# schematic.net
KiCad netlist of a schematic drawn in EAGLE
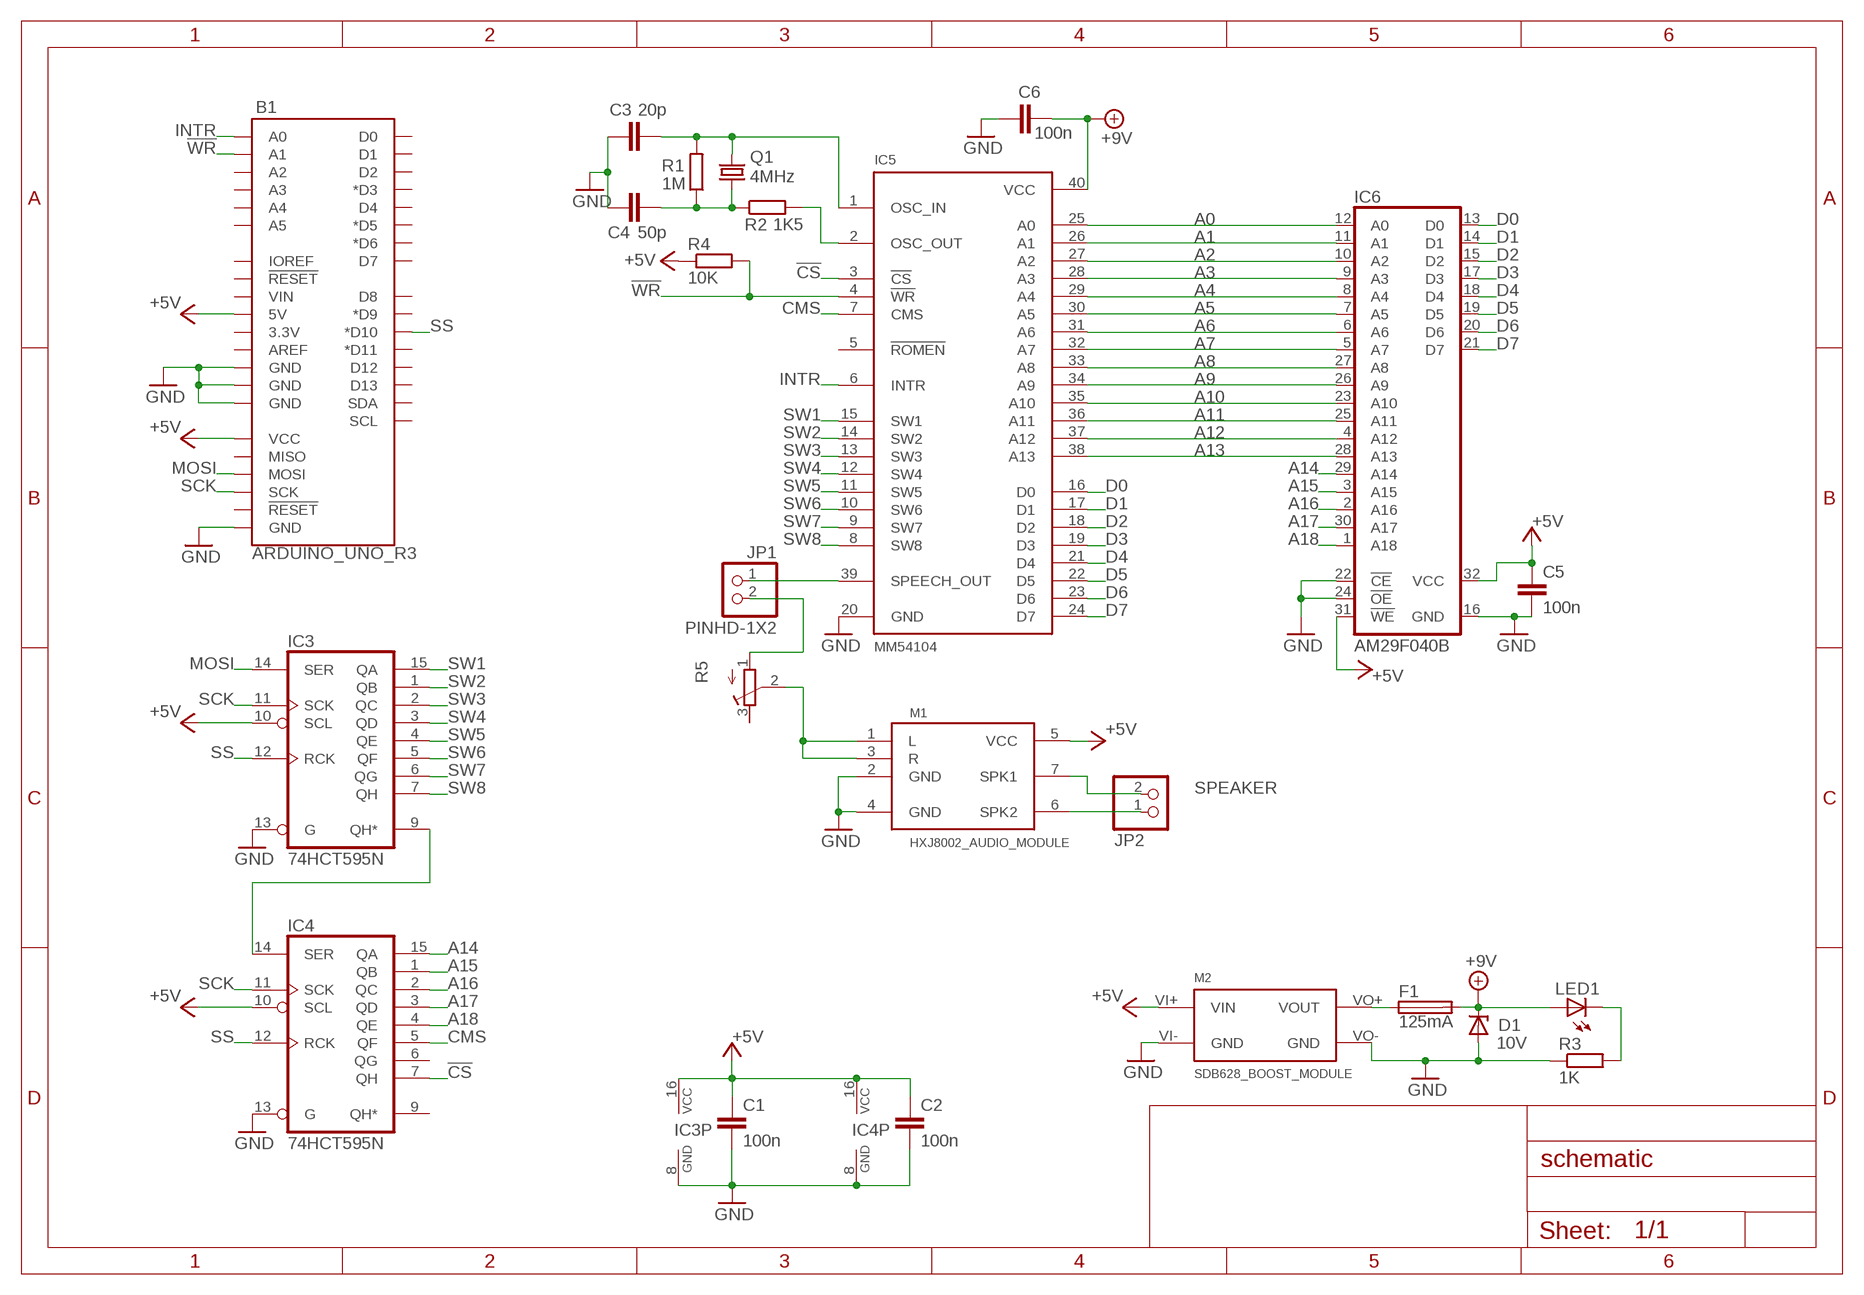
[diagram p0: schematic, sheet 1]

(export (version "E")
  (design (tool "Eeschema 10.0.6"))
  (components
    (comp (ref "B1")
      (value "ARDUINO_UNO_R3")
      (footprint "eagle-import:ARDUINO_R3")
      (libsource (lib "eagle-import") (part "ARDUINO_UNO_R3"))
    )
    (comp (ref "C1")
      (value "100n")
      (footprint "eagle-import:C0805K")
      (libsource (lib "eagle-import") (part "C-EUC0805K"))
    )
    (comp (ref "C2")
      (value "100n")
      (footprint "eagle-import:C0805K")
      (libsource (lib "eagle-import") (part "C-EUC0805K"))
    )
    (comp (ref "C3")
      (value "20p")
      (footprint "eagle-import:C0805K")
      (libsource (lib "eagle-import") (part "C-EUC0805K"))
    )
    (comp (ref "C4")
      (value "50p")
      (footprint "eagle-import:C0805K")
      (libsource (lib "eagle-import") (part "C-EUC0805K"))
    )
    (comp (ref "C5")
      (value "100n")
      (footprint "eagle-import:C0805K")
      (libsource (lib "eagle-import") (part "C-EUC0805K"))
    )
    (comp (ref "C6")
      (value "100n")
      (footprint "eagle-import:C0805K")
      (libsource (lib "eagle-import") (part "C-EUC0805K"))
    )
    (comp (ref "D1")
      (value "10V")
      (footprint "eagle-import:F126Z12")
      (libsource (lib "eagle-import") (part "ZENER-DIODEF126-12"))
    )
    (comp (ref "F1")
      (value "125mA")
      (footprint "eagle-import:TE5")
      (libsource (lib "eagle-import") (part "FUSETE5"))
    )
    (comp (ref "IC3")
      (value "74HCT595N")
      (footprint "eagle-import:DIL16")
      (libsource (lib "eagle-import") (part "74595NHCT"))
    )
    (comp (ref "IC4")
      (value "74HCT595N")
      (footprint "eagle-import:DIL16")
      (libsource (lib "eagle-import") (part "74595NHCT"))
    )
    (comp (ref "IC5")
      (value "MM54104")
      (footprint "eagle-import:DIL40")
      (libsource (lib "eagle-import") (part "MM54104"))
    )
    (comp (ref "IC6")
      (value "AM29F040B")
      (footprint "eagle-import:PLCC32")
      (libsource (lib "eagle-import") (part "AM29F040B"))
    )
    (comp (ref "JP1")
      (value "PINHD-1X2")
      (footprint "eagle-import:1X02")
      (libsource (lib "eagle-import") (part "PINHD-1X2"))
    )
    (comp (ref "JP2")
      (value "PINHD-1X2/90")
      (footprint "eagle-import:1X02_90")
      (libsource (lib "eagle-import") (part "PINHD-1X2/90"))
    )
    (comp (ref "LED1")
      (value "LEDCHIPLED_1206")
      (footprint "eagle-import:CHIPLED_1206")
      (libsource (lib "eagle-import") (part "LEDCHIPLED_1206"))
    )
    (comp (ref "M1")
      (value "HXJ8002_AUDIO_MODULE")
      (footprint "eagle-import:HXJ8002")
      (libsource (lib "eagle-import") (part "HXJ8002_AUDIO_MODULE"))
    )
    (comp (ref "M2")
      (value "SDB628_BOOST_MODULE")
      (footprint "eagle-import:SDB628_MODULE")
      (libsource (lib "eagle-import") (part "SDB628_BOOST_MODULE"))
    )
    (comp (ref "Q1")
      (value "4MHz")
      (footprint "eagle-import:HC49_S")
      (libsource (lib "eagle-import") (part "CRYSTALHC49S"))
    )
    (comp (ref "R1")
      (value "1M")
      (footprint "eagle-import:R0805")
      (libsource (lib "eagle-import") (part "R-EU_R0805"))
    )
    (comp (ref "R2")
      (value "1K5")
      (footprint "eagle-import:R0805")
      (libsource (lib "eagle-import") (part "R-EU_R0805"))
    )
    (comp (ref "R3")
      (value "1K")
      (footprint "eagle-import:R0805W")
      (libsource (lib "eagle-import") (part "R-EU_R0805W"))
    )
    (comp (ref "R4")
      (value "10K")
      (footprint "eagle-import:R0805W")
      (libsource (lib "eagle-import") (part "R-EU_R0805W"))
    )
    (comp (ref "R5")
      (value "R-TRIMM3296W")
      (footprint "eagle-import:RTRIM3296W")
      (libsource (lib "eagle-import") (part "R-TRIMM3296W"))
    )
  )
  (nets
    (net (code "1") (name "+5V") (class "Default")
      (node (ref "B1") (pin "5V") (pinfunction "5V_5V") (pintype "bidirectional"))
      (node (ref "B1") (pin "VCC") (pinfunction "VCC_VCC") (pintype "bidirectional"))
      (node (ref "C1") (pin "1") (pinfunction "1_1") (pintype "passive"))
      (node (ref "C2") (pin "1") (pinfunction "1_1") (pintype "passive"))
      (node (ref "C5") (pin "1") (pinfunction "1_1") (pintype "passive"))
      (node (ref "IC3") (pin "10") (pinfunction "SCL_10") (pintype "input"))
      (node (ref "IC3") (pin "16") (pinfunction "VCC_16") (pintype "power_in"))
      (node (ref "IC4") (pin "10") (pinfunction "SCL_10") (pintype "input"))
      (node (ref "IC4") (pin "16") (pinfunction "VCC_16") (pintype "power_in"))
      (node (ref "IC6") (pin "31") (pinfunction "~{WE}_31") (pintype "input"))
      (node (ref "IC6") (pin "32") (pinfunction "VCC_32") (pintype "power_in"))
      (node (ref "M1") (pin "5") (pinfunction "VCC_5") (pintype "power_in"))
      (node (ref "M2") (pin "VI+") (pinfunction "VIN_VI+") (pintype "power_in"))
      (node (ref "R4") (pin "1") (pinfunction "1_1") (pintype "passive"))
    )
    (net (code "2") (name "+9V") (class "Default")
      (node (ref "C6") (pin "2") (pinfunction "2_2") (pintype "passive"))
      (node (ref "D1") (pin "C") (pinfunction "C_C") (pintype "passive"))
      (node (ref "F1") (pin "2") (pinfunction "2_2") (pintype "passive"))
      (node (ref "IC5") (pin "40") (pinfunction "VCC_40") (pintype "power_in"))
      (node (ref "LED1") (pin "A") (pinfunction "A_A") (pintype "passive"))
    )
    (net (code "3") (name "/A0") (class "Default")
      (node (ref "IC5") (pin "25") (pinfunction "A0_25") (pintype "output"))
      (node (ref "IC6") (pin "12") (pinfunction "A0_12") (pintype "input"))
    )
    (net (code "4") (name "/A1") (class "Default")
      (node (ref "IC5") (pin "26") (pinfunction "A1_26") (pintype "output"))
      (node (ref "IC6") (pin "11") (pinfunction "A1_11") (pintype "input"))
    )
    (net (code "5") (name "/A2") (class "Default")
      (node (ref "IC5") (pin "27") (pinfunction "A2_27") (pintype "output"))
      (node (ref "IC6") (pin "10") (pinfunction "A2_10") (pintype "input"))
    )
    (net (code "6") (name "/A3") (class "Default")
      (node (ref "IC5") (pin "28") (pinfunction "A3_28") (pintype "output"))
      (node (ref "IC6") (pin "9") (pinfunction "A3_9") (pintype "input"))
    )
    (net (code "7") (name "/A4") (class "Default")
      (node (ref "IC5") (pin "29") (pinfunction "A4_29") (pintype "output"))
      (node (ref "IC6") (pin "8") (pinfunction "A4_8") (pintype "input"))
    )
    (net (code "8") (name "/A5") (class "Default")
      (node (ref "IC5") (pin "30") (pinfunction "A5_30") (pintype "output"))
      (node (ref "IC6") (pin "7") (pinfunction "A5_7") (pintype "input"))
    )
    (net (code "9") (name "/A6") (class "Default")
      (node (ref "IC5") (pin "31") (pinfunction "A6_31") (pintype "output"))
      (node (ref "IC6") (pin "6") (pinfunction "A6_6") (pintype "input"))
    )
    (net (code "10") (name "/A7") (class "Default")
      (node (ref "IC5") (pin "32") (pinfunction "A7_32") (pintype "output"))
      (node (ref "IC6") (pin "5") (pinfunction "A7_5") (pintype "input"))
    )
    (net (code "11") (name "/A8") (class "Default")
      (node (ref "IC5") (pin "33") (pinfunction "A8_33") (pintype "output"))
      (node (ref "IC6") (pin "27") (pinfunction "A8_27") (pintype "input"))
    )
    (net (code "12") (name "/A9") (class "Default")
      (node (ref "IC5") (pin "34") (pinfunction "A9_34") (pintype "output"))
      (node (ref "IC6") (pin "26") (pinfunction "A9_26") (pintype "input"))
    )
    (net (code "13") (name "/A10") (class "Default")
      (node (ref "IC5") (pin "35") (pinfunction "A10_35") (pintype "output"))
      (node (ref "IC6") (pin "23") (pinfunction "A10_23") (pintype "input"))
    )
    (net (code "14") (name "/A11") (class "Default")
      (node (ref "IC5") (pin "36") (pinfunction "A11_36") (pintype "output"))
      (node (ref "IC6") (pin "25") (pinfunction "A11_25") (pintype "input"))
    )
    (net (code "15") (name "/A12") (class "Default")
      (node (ref "IC5") (pin "37") (pinfunction "A12_37") (pintype "output"))
      (node (ref "IC6") (pin "4") (pinfunction "A12_4") (pintype "input"))
    )
    (net (code "16") (name "/A13") (class "Default")
      (node (ref "IC5") (pin "38") (pinfunction "A13_38") (pintype "output"))
      (node (ref "IC6") (pin "28") (pinfunction "A13_28") (pintype "input"))
    )
    (net (code "17") (name "/A14") (class "Default")
      (node (ref "IC4") (pin "15") (pinfunction "QA_15") (pintype "tri_state"))
      (node (ref "IC6") (pin "29") (pinfunction "A14_29") (pintype "input"))
    )
    (net (code "18") (name "/A15") (class "Default")
      (node (ref "IC4") (pin "1") (pinfunction "QB_1") (pintype "tri_state"))
      (node (ref "IC6") (pin "3") (pinfunction "A15_3") (pintype "input"))
    )
    (net (code "19") (name "/A16") (class "Default")
      (node (ref "IC4") (pin "2") (pinfunction "QC_2") (pintype "tri_state"))
      (node (ref "IC6") (pin "2") (pinfunction "A16_2") (pintype "input"))
    )
    (net (code "20") (name "/A17") (class "Default")
      (node (ref "IC4") (pin "3") (pinfunction "QD_3") (pintype "tri_state"))
      (node (ref "IC6") (pin "30") (pinfunction "A17_30") (pintype "input"))
    )
    (net (code "21") (name "/A18") (class "Default")
      (node (ref "IC4") (pin "4") (pinfunction "QE_4") (pintype "tri_state"))
      (node (ref "IC6") (pin "1") (pinfunction "A18_1") (pintype "input"))
    )
    (net (code "22") (name "/CMS") (class "Default")
      (node (ref "IC4") (pin "5") (pinfunction "QF_5") (pintype "tri_state"))
      (node (ref "IC5") (pin "7") (pinfunction "CMS_7") (pintype "input"))
    )
    (net (code "23") (name "/D0") (class "Default")
      (node (ref "IC5") (pin "16") (pinfunction "D0_16") (pintype "bidirectional"))
      (node (ref "IC6") (pin "13") (pinfunction "D0_13") (pintype "tri_state"))
    )
    (net (code "24") (name "/D1") (class "Default")
      (node (ref "IC5") (pin "17") (pinfunction "D1_17") (pintype "bidirectional"))
      (node (ref "IC6") (pin "14") (pinfunction "D1_14") (pintype "tri_state"))
    )
    (net (code "25") (name "/D2") (class "Default")
      (node (ref "IC5") (pin "18") (pinfunction "D2_18") (pintype "bidirectional"))
      (node (ref "IC6") (pin "15") (pinfunction "D2_15") (pintype "tri_state"))
    )
    (net (code "26") (name "/D3") (class "Default")
      (node (ref "IC5") (pin "19") (pinfunction "D3_19") (pintype "bidirectional"))
      (node (ref "IC6") (pin "17") (pinfunction "D3_17") (pintype "tri_state"))
    )
    (net (code "27") (name "/D4") (class "Default")
      (node (ref "IC5") (pin "21") (pinfunction "D4_21") (pintype "bidirectional"))
      (node (ref "IC6") (pin "18") (pinfunction "D4_18") (pintype "tri_state"))
    )
    (net (code "28") (name "/D5") (class "Default")
      (node (ref "IC5") (pin "22") (pinfunction "D5_22") (pintype "bidirectional"))
      (node (ref "IC6") (pin "19") (pinfunction "D5_19") (pintype "tri_state"))
    )
    (net (code "29") (name "/D6") (class "Default")
      (node (ref "IC5") (pin "23") (pinfunction "D6_23") (pintype "bidirectional"))
      (node (ref "IC6") (pin "20") (pinfunction "D6_20") (pintype "tri_state"))
    )
    (net (code "30") (name "/D7") (class "Default")
      (node (ref "IC5") (pin "24") (pinfunction "D7_24") (pintype "bidirectional"))
      (node (ref "IC6") (pin "21") (pinfunction "D7_21") (pintype "tri_state"))
    )
    (net (code "31") (name "/INTR") (class "Default")
      (node (ref "B1") (pin "A0") (pinfunction "A0_A0") (pintype "bidirectional"))
      (node (ref "IC5") (pin "6") (pinfunction "INTR_6") (pintype "output"))
    )
    (net (code "32") (name "/MOSI") (class "Default")
      (node (ref "B1") (pin "MOSI") (pinfunction "MOSI_MOSI") (pintype "bidirectional"))
      (node (ref "IC3") (pin "14") (pinfunction "SER_14") (pintype "input"))
    )
    (net (code "33") (name "/SCK") (class "Default")
      (node (ref "B1") (pin "SCK") (pinfunction "SCK_SCK") (pintype "bidirectional"))
      (node (ref "IC3") (pin "11") (pinfunction "SCK_11") (pintype "input"))
      (node (ref "IC4") (pin "11") (pinfunction "SCK_11") (pintype "input"))
    )
    (net (code "34") (name "/SS") (class "Default")
      (node (ref "B1") (pin "D10") (pinfunction "*D10_D10") (pintype "bidirectional"))
      (node (ref "IC3") (pin "12") (pinfunction "RCK_12") (pintype "input"))
      (node (ref "IC4") (pin "12") (pinfunction "RCK_12") (pintype "input"))
    )
    (net (code "35") (name "/SW1") (class "Default")
      (node (ref "IC3") (pin "15") (pinfunction "QA_15") (pintype "tri_state"))
      (node (ref "IC5") (pin "15") (pinfunction "SW1_15") (pintype "input"))
    )
    (net (code "36") (name "/SW2") (class "Default")
      (node (ref "IC3") (pin "1") (pinfunction "QB_1") (pintype "tri_state"))
      (node (ref "IC5") (pin "14") (pinfunction "SW2_14") (pintype "input"))
    )
    (net (code "37") (name "/SW3") (class "Default")
      (node (ref "IC3") (pin "2") (pinfunction "QC_2") (pintype "tri_state"))
      (node (ref "IC5") (pin "13") (pinfunction "SW3_13") (pintype "input"))
    )
    (net (code "38") (name "/SW4") (class "Default")
      (node (ref "IC3") (pin "3") (pinfunction "QD_3") (pintype "tri_state"))
      (node (ref "IC5") (pin "12") (pinfunction "SW4_12") (pintype "input"))
    )
    (net (code "39") (name "/SW5") (class "Default")
      (node (ref "IC3") (pin "4") (pinfunction "QE_4") (pintype "tri_state"))
      (node (ref "IC5") (pin "11") (pinfunction "SW5_11") (pintype "input"))
    )
    (net (code "40") (name "/SW6") (class "Default")
      (node (ref "IC3") (pin "5") (pinfunction "QF_5") (pintype "tri_state"))
      (node (ref "IC5") (pin "10") (pinfunction "SW6_10") (pintype "input"))
    )
    (net (code "41") (name "/SW7") (class "Default")
      (node (ref "IC3") (pin "6") (pinfunction "QG_6") (pintype "tri_state"))
      (node (ref "IC5") (pin "9") (pinfunction "SW7_9") (pintype "input"))
    )
    (net (code "42") (name "/SW8") (class "Default")
      (node (ref "IC3") (pin "7") (pinfunction "QH_7") (pintype "tri_state"))
      (node (ref "IC5") (pin "8") (pinfunction "SW8_8") (pintype "input"))
    )
    (net (code "43") (name "/~{CS}") (class "Default")
      (node (ref "IC4") (pin "7") (pinfunction "QH_7") (pintype "tri_state"))
      (node (ref "IC5") (pin "3") (pinfunction "~{CS}_3") (pintype "input"))
    )
    (net (code "44") (name "/~{WR}") (class "Default")
      (node (ref "B1") (pin "A1") (pinfunction "A1_A1") (pintype "bidirectional"))
      (node (ref "IC5") (pin "4") (pinfunction "~{WR}_4") (pintype "input"))
      (node (ref "R4") (pin "2") (pinfunction "2_2") (pintype "passive"))
    )
    (net (code "45") (name "GND") (class "Default")
      (node (ref "B1") (pin "GND@1") (pinfunction "GND_GND@1") (pintype "bidirectional"))
      (node (ref "B1") (pin "GND@2") (pinfunction "GND_GND@2") (pintype "bidirectional"))
      (node (ref "B1") (pin "GND@3") (pinfunction "GND_GND@3") (pintype "bidirectional"))
      (node (ref "B1") (pin "GND@4") (pinfunction "GND_GND@4") (pintype "bidirectional"))
      (node (ref "C1") (pin "2") (pinfunction "2_2") (pintype "passive"))
      (node (ref "C2") (pin "2") (pinfunction "2_2") (pintype "passive"))
      (node (ref "C3") (pin "1") (pinfunction "1_1") (pintype "passive"))
      (node (ref "C4") (pin "1") (pinfunction "1_1") (pintype "passive"))
      (node (ref "C5") (pin "2") (pinfunction "2_2") (pintype "passive"))
      (node (ref "C6") (pin "1") (pinfunction "1_1") (pintype "passive"))
      (node (ref "D1") (pin "A") (pinfunction "A_A") (pintype "passive"))
      (node (ref "IC3") (pin "13") (pinfunction "G_13") (pintype "input"))
      (node (ref "IC3") (pin "8") (pinfunction "GND_8") (pintype "power_in"))
      (node (ref "IC4") (pin "13") (pinfunction "G_13") (pintype "input"))
      (node (ref "IC4") (pin "8") (pinfunction "GND_8") (pintype "power_in"))
      (node (ref "IC5") (pin "20") (pinfunction "GND_20") (pintype "power_in"))
      (node (ref "IC6") (pin "16") (pinfunction "GND_16") (pintype "power_in"))
      (node (ref "IC6") (pin "22") (pinfunction "~{CE}_22") (pintype "input"))
      (node (ref "IC6") (pin "24") (pinfunction "~{OE}_24") (pintype "input"))
      (node (ref "M1") (pin "2") (pinfunction "GND_2") (pintype "power_in"))
      (node (ref "M1") (pin "4") (pinfunction "GND_4") (pintype "power_in"))
      (node (ref "M2") (pin "VI-") (pinfunction "GND_VI-") (pintype "power_in"))
      (node (ref "M2") (pin "VO-") (pinfunction "GND_VO-") (pintype "power_in"))
      (node (ref "R3") (pin "1") (pinfunction "1_1") (pintype "passive"))
    )
    (net (code "46") (name "Net-(C4-Pad2)") (class "Default")
      (node (ref "C4") (pin "2") (pinfunction "2_2") (pintype "passive"))
      (node (ref "Q1") (pin "1") (pinfunction "1_1") (pintype "passive"))
      (node (ref "R1") (pin "1") (pinfunction "1_1") (pintype "passive"))
      (node (ref "R2") (pin "1") (pinfunction "1_1") (pintype "passive"))
    )
    (net (code "47") (name "Net-(IC3A-QH*)") (class "Default")
      (node (ref "IC3") (pin "9") (pinfunction "QH*_9") (pintype "tri_state"))
      (node (ref "IC4") (pin "14") (pinfunction "SER_14") (pintype "input"))
    )
    (net (code "48") (name "Net-(IC5-OSC_IN)") (class "Default")
      (node (ref "C3") (pin "2") (pinfunction "2_2") (pintype "passive"))
      (node (ref "IC5") (pin "1") (pinfunction "OSC_IN_1") (pintype "bidirectional"))
      (node (ref "Q1") (pin "2") (pinfunction "2_2") (pintype "passive"))
      (node (ref "R1") (pin "2") (pinfunction "2_2") (pintype "passive"))
    )
    (net (code "49") (name "Net-(IC5-OSC_OUT)") (class "Default")
      (node (ref "IC5") (pin "2") (pinfunction "OSC_OUT_2") (pintype "bidirectional"))
      (node (ref "R2") (pin "2") (pinfunction "2_2") (pintype "passive"))
    )
    (net (code "50") (name "Net-(IC5-SPEECH_OUT)") (class "Default")
      (node (ref "IC5") (pin "39") (pinfunction "SPEECH_OUT_39") (pintype "output"))
      (node (ref "JP1") (pin "1") (pinfunction "1_1") (pintype "passive"))
    )
    (net (code "51") (name "Net-(LED1-PadC)") (class "Default")
      (node (ref "LED1") (pin "C") (pinfunction "C_C") (pintype "passive"))
      (node (ref "R3") (pin "2") (pinfunction "2_2") (pintype "passive"))
    )
    (net (code "52") (name "Net-(M1-L)") (class "Default")
      (node (ref "M1") (pin "1") (pinfunction "L_1") (pintype "input"))
      (node (ref "M1") (pin "3") (pinfunction "R_3") (pintype "input"))
      (node (ref "R5") (pin "2") (pinfunction "S_2") (pintype "passive"))
    )
    (net (code "53") (name "Net-(M1-SPK1)") (class "Default")
      (node (ref "JP2") (pin "2") (pinfunction "2_2") (pintype "passive"))
      (node (ref "M1") (pin "7") (pinfunction "SPK1_7") (pintype "output"))
    )
    (net (code "54") (name "Net-(M1-SPK2)") (class "Default")
      (node (ref "JP2") (pin "1") (pinfunction "1_1") (pintype "passive"))
      (node (ref "M1") (pin "6") (pinfunction "SPK2_6") (pintype "output"))
    )
    (net (code "55") (name "Net-(M2-VOUT)") (class "Default")
      (node (ref "F1") (pin "1") (pinfunction "1_1") (pintype "passive"))
      (node (ref "M2") (pin "VO+") (pinfunction "VOUT_VO+") (pintype "power_in"))
    )
    (net (code "56") (name "Net-(R5-A)") (class "Default")
      (node (ref "JP1") (pin "2") (pinfunction "2_2") (pintype "passive"))
      (node (ref "R5") (pin "1") (pinfunction "A_1") (pintype "passive"))
    )
    (net (code "57") (name "unconnected-(B1-*D3-PadD3)") (class "Default")
      (node (ref "B1") (pin "D3") (pinfunction "*D3_D3") (pintype "bidirectional"))
    )
    (net (code "58") (name "unconnected-(B1-*D5-PadD5)") (class "Default")
      (node (ref "B1") (pin "D5") (pinfunction "*D5_D5") (pintype "bidirectional"))
    )
    (net (code "59") (name "unconnected-(B1-*D6-PadD6)") (class "Default")
      (node (ref "B1") (pin "D6") (pinfunction "*D6_D6") (pintype "bidirectional"))
    )
    (net (code "60") (name "unconnected-(B1-*D9-PadD9)") (class "Default")
      (node (ref "B1") (pin "D9") (pinfunction "*D9_D9") (pintype "bidirectional"))
    )
    (net (code "61") (name "unconnected-(B1-*D11-PadD11)") (class "Default")
      (node (ref "B1") (pin "D11") (pinfunction "*D11_D11") (pintype "bidirectional"))
    )
    (net (code "62") (name "unconnected-(B1-Pad3.3V)") (class "Default")
      (node (ref "B1") (pin "3.3V") (pinfunction "3.3V_3.3V") (pintype "bidirectional"))
    )
    (net (code "63") (name "unconnected-(B1-PadA2)") (class "Default")
      (node (ref "B1") (pin "A2") (pinfunction "A2_A2") (pintype "bidirectional"))
    )
    (net (code "64") (name "unconnected-(B1-PadA3)") (class "Default")
      (node (ref "B1") (pin "A3") (pinfunction "A3_A3") (pintype "bidirectional"))
    )
    (net (code "65") (name "unconnected-(B1-PadA4)") (class "Default")
      (node (ref "B1") (pin "A4") (pinfunction "A4_A4") (pintype "bidirectional"))
    )
    (net (code "66") (name "unconnected-(B1-PadA5)") (class "Default")
      (node (ref "B1") (pin "A5") (pinfunction "A5_A5") (pintype "bidirectional"))
    )
    (net (code "67") (name "unconnected-(B1-PadAREF)") (class "Default")
      (node (ref "B1") (pin "AREF") (pinfunction "AREF_AREF") (pintype "bidirectional"))
    )
    (net (code "68") (name "unconnected-(B1-PadD0)") (class "Default")
      (node (ref "B1") (pin "D0") (pinfunction "D0_D0") (pintype "bidirectional"))
    )
    (net (code "69") (name "unconnected-(B1-PadD1)") (class "Default")
      (node (ref "B1") (pin "D1") (pinfunction "D1_D1") (pintype "bidirectional"))
    )
    (net (code "70") (name "unconnected-(B1-PadD2)") (class "Default")
      (node (ref "B1") (pin "D2") (pinfunction "D2_D2") (pintype "bidirectional"))
    )
    (net (code "71") (name "unconnected-(B1-PadD4)") (class "Default")
      (node (ref "B1") (pin "D4") (pinfunction "D4_D4") (pintype "bidirectional"))
    )
    (net (code "72") (name "unconnected-(B1-PadD7)") (class "Default")
      (node (ref "B1") (pin "D7") (pinfunction "D7_D7") (pintype "bidirectional"))
    )
    (net (code "73") (name "unconnected-(B1-PadD8)") (class "Default")
      (node (ref "B1") (pin "D8") (pinfunction "D8_D8") (pintype "bidirectional"))
    )
    (net (code "74") (name "unconnected-(B1-PadD12)") (class "Default")
      (node (ref "B1") (pin "D12") (pinfunction "D12_D12") (pintype "bidirectional"))
    )
    (net (code "75") (name "unconnected-(B1-PadD13)") (class "Default")
      (node (ref "B1") (pin "D13") (pinfunction "D13_D13") (pintype "bidirectional"))
    )
    (net (code "76") (name "unconnected-(B1-PadIOREF)") (class "Default")
      (node (ref "B1") (pin "IOREF") (pinfunction "IOREF_IOREF") (pintype "bidirectional"))
    )
    (net (code "77") (name "unconnected-(B1-PadMISO)") (class "Default")
      (node (ref "B1") (pin "MISO") (pinfunction "MISO_MISO") (pintype "bidirectional"))
    )
    (net (code "78") (name "unconnected-(B1-PadSCL)") (class "Default")
      (node (ref "B1") (pin "SCL") (pinfunction "SCL_SCL") (pintype "bidirectional"))
    )
    (net (code "79") (name "unconnected-(B1-PadSDA)") (class "Default")
      (node (ref "B1") (pin "SDA") (pinfunction "SDA_SDA") (pintype "bidirectional"))
    )
    (net (code "80") (name "unconnected-(B1-PadVIN)") (class "Default")
      (node (ref "B1") (pin "VIN") (pinfunction "VIN_VIN") (pintype "bidirectional"))
    )
    (net (code "81") (name "unconnected-(B1-~{RESET}-PadRESET@1)") (class "Default")
      (node (ref "B1") (pin "RESET@1") (pinfunction "~{RESET}_RESET@1") (pintype "bidirectional"))
    )
    (net (code "82") (name "unconnected-(B1-~{RESET}-PadRESET@2)") (class "Default")
      (node (ref "B1") (pin "RESET@2") (pinfunction "~{RESET}_RESET@2") (pintype "bidirectional"))
    )
    (net (code "83") (name "unconnected-(IC4A-QG-Pad6)") (class "Default")
      (node (ref "IC4") (pin "6") (pinfunction "QG_6") (pintype "tri_state"))
    )
    (net (code "84") (name "unconnected-(IC4A-QH*-Pad9)") (class "Default")
      (node (ref "IC4") (pin "9") (pinfunction "QH*_9") (pintype "tri_state"))
    )
    (net (code "85") (name "unconnected-(IC5-~{ROMEN}-Pad5)") (class "Default")
      (node (ref "IC5") (pin "5") (pinfunction "~{ROMEN}_5") (pintype "output"))
    )
    (net (code "86") (name "unconnected-(R5-E-Pad3)") (class "Default")
      (node (ref "R5") (pin "3") (pinfunction "E_3") (pintype "passive"))
    )
  )
)
